# hdmi_to_8pin_header.net
KiCad netlist of a schematic drawn in Altium Designer
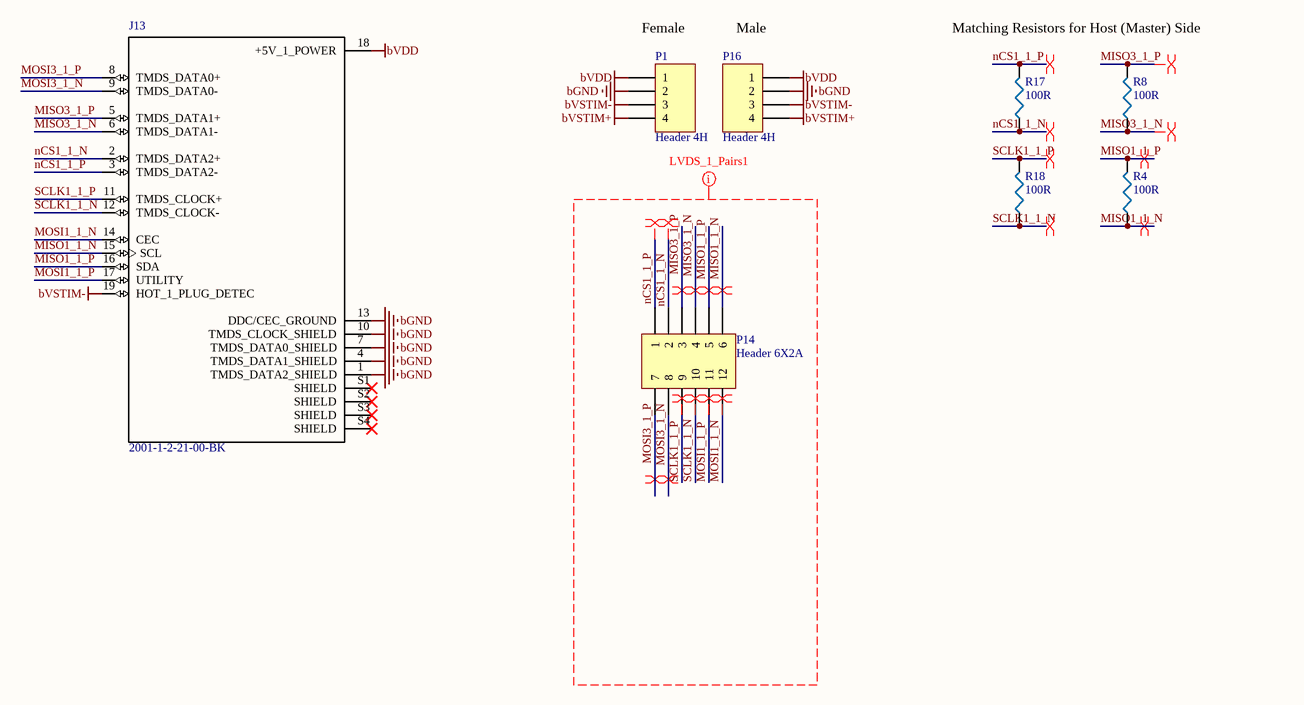
[diagram p0: hdmi_to_8pin_header.SchDoc]

(export (version "E")
  (design (tool "Eeschema 10.0.6"))
  (components
    (comp (ref "J13")
      (value "2001-1-2-21-00-BK")
      (footprint "*CNC_2001-1-2-21-00-BK_2001-1-2-21-00-BK(Primary)")
      (description "Mini Hdmi 19p Female Smt")
      (fields (field (name "DIGI-KEY_PART_NUMBER") "1175-1704-1-ND") (field (name "MANUFACTURER") "CNC Tech"))
      (libsource (lib "cnc_hdmi") (part "2001-1-2-21-00-BK"))
    )
    (comp (ref "P1")
      (value "Header 4H")
      (footprint "sullins_conn_headers:PPTC041LGBN-RC")
      (description "Header, 4-Pin, Right Angle")
      (fields
        (field (name "MANUFACTURER") "Sullins Connector Solutions")
        (field (name "MANUFACTURER PART NUMBER") "PPTC041LGBN-RC")
        (field (name "PUBLISHER") "Altium Limited")
      )
      (libsource (lib "") (part "Header 4H_1"))
    )
    (comp (ref "P14")
      (value "Header 6X2A")
      (footprint "sullins_conn_headers:PPPC062LJBN-RC")
      (description "Header, 6-Pin, Dual row")
      (fields
        (field (name "MANUFACTURER") "Sullins Connector Solutions")
        (field (name "MANUFACTURER PART NUMBER") "PPPC062LJBN-RC")
        (field (name "PUBLISHER") "Altium Limited")
      )
      (libsource (lib "Miscellaneous Connectors") (part "Header 6X2A"))
    )
    (comp (ref "P16")
      (value "Header 4H")
      (footprint "sullins_conn_headers:PEC04SBAN")
      (description "Header, 4-Pin, Right Angle")
      (fields
        (field (name "MANUFACTURER") "Sullins Connector Solutions")
        (field (name "MANUFACTURER PART NUMBER") "PEC04SBAN")
        (field (name "PUBLISHER") "Altium Limited")
      )
      (libsource (lib "Miscellaneous Connectors") (part "Header 4H"))
    )
    (comp (ref "R4")
      (value "100R")
      (footprint "standard_components:R0805")
      (description "ERJ-6ENF1000V")
      (fields (field (name "MANUFACTURER") "Panasonic Electronic Components") (field (name "TOLERANCE") "1%"))
      (libsource (lib "standard_components") (part "RES100"))
    )
    (comp (ref "R8")
      (value "100R")
      (footprint "standard_components:R0805")
      (description "ERJ-6ENF1000V")
      (fields (field (name "MANUFACTURER") "Panasonic Electronic Components") (field (name "TOLERANCE") "1%"))
      (libsource (lib "standard_components") (part "RES100"))
    )
    (comp (ref "R17")
      (value "100R")
      (footprint "standard_components:R0805")
      (description "ERJ-6ENF1000V")
      (fields (field (name "MANUFACTURER") "Panasonic Electronic Components") (field (name "TOLERANCE") "1%"))
      (libsource (lib "standard_components") (part "RES100"))
    )
    (comp (ref "R18")
      (value "100R")
      (footprint "standard_components:R0805")
      (description "ERJ-6ENF1000V")
      (fields (field (name "MANUFACTURER") "Panasonic Electronic Components") (field (name "TOLERANCE") "1%"))
      (libsource (lib "standard_components") (part "RES100"))
    )
  )
  (nets
    (net (code "1") (name "/MISO1_1_N") (class "Default")
      (node (ref "J13") (pin "15") (pinfunction "SCL_15") (pintype "bidirectional"))
      (node (ref "P14") (pin "6") (pinfunction "6_6") (pintype "passive"))
      (node (ref "R4") (pin "1") (pinfunction "1_1") (pintype "passive"))
    )
    (net (code "2") (name "/MISO1_1_P") (class "Default")
      (node (ref "J13") (pin "16") (pinfunction "SDA_16") (pintype "bidirectional"))
      (node (ref "P14") (pin "5") (pinfunction "5_5") (pintype "passive"))
      (node (ref "R4") (pin "2") (pinfunction "2_2") (pintype "passive"))
    )
    (net (code "3") (name "/MISO3_1_N") (class "Default")
      (node (ref "J13") (pin "6") (pinfunction "TMDS_DATA1-_6") (pintype "bidirectional"))
      (node (ref "P14") (pin "4") (pinfunction "4_4") (pintype "passive"))
      (node (ref "R8") (pin "1") (pinfunction "1_1") (pintype "passive"))
    )
    (net (code "4") (name "/MISO3_1_P") (class "Default")
      (node (ref "J13") (pin "5") (pinfunction "TMDS_DATA1+_5") (pintype "bidirectional"))
      (node (ref "P14") (pin "3") (pinfunction "3_3") (pintype "passive"))
      (node (ref "R8") (pin "2") (pinfunction "2_2") (pintype "passive"))
    )
    (net (code "5") (name "/MOSI1_1_N") (class "Default")
      (node (ref "J13") (pin "14") (pinfunction "CEC_14") (pintype "bidirectional"))
      (node (ref "P14") (pin "12") (pinfunction "12_12") (pintype "passive"))
    )
    (net (code "6") (name "/MOSI1_1_P") (class "Default")
      (node (ref "J13") (pin "17") (pinfunction "UTILITY_17") (pintype "bidirectional"))
      (node (ref "P14") (pin "11") (pinfunction "11_11") (pintype "passive"))
    )
    (net (code "7") (name "/MOSI3_1_N") (class "Default")
      (node (ref "J13") (pin "9") (pinfunction "TMDS_DATA0-_9") (pintype "bidirectional"))
      (node (ref "P14") (pin "8") (pinfunction "8_8") (pintype "passive"))
    )
    (net (code "8") (name "/MOSI3_1_P") (class "Default")
      (node (ref "J13") (pin "8") (pinfunction "TMDS_DATA0+_8") (pintype "bidirectional"))
      (node (ref "P14") (pin "7") (pinfunction "7_7") (pintype "passive"))
    )
    (net (code "9") (name "/SCLK1_1_N") (class "Default")
      (node (ref "J13") (pin "12") (pinfunction "TMDS_CLOCK-_12") (pintype "bidirectional"))
      (node (ref "P14") (pin "10") (pinfunction "10_10") (pintype "passive"))
      (node (ref "R18") (pin "1") (pinfunction "1_1") (pintype "passive"))
    )
    (net (code "10") (name "/SCLK1_1_P") (class "Default")
      (node (ref "J13") (pin "11") (pinfunction "TMDS_CLOCK+_11") (pintype "bidirectional"))
      (node (ref "P14") (pin "9") (pinfunction "9_9") (pintype "passive"))
      (node (ref "R18") (pin "2") (pinfunction "2_2") (pintype "passive"))
    )
    (net (code "11") (name "/nCS1_1_N") (class "Default")
      (node (ref "J13") (pin "2") (pinfunction "TMDS_DATA2+_2") (pintype "bidirectional"))
      (node (ref "P14") (pin "2") (pinfunction "2_2") (pintype "passive"))
      (node (ref "R17") (pin "1") (pinfunction "1_1") (pintype "passive"))
    )
    (net (code "12") (name "/nCS1_1_P") (class "Default")
      (node (ref "J13") (pin "3") (pinfunction "TMDS_DATA2-_3") (pintype "bidirectional"))
      (node (ref "P14") (pin "1") (pinfunction "1_1") (pintype "passive"))
      (node (ref "R17") (pin "2") (pinfunction "2_2") (pintype "passive"))
    )
    (net (code "13") (name "bGND") (class "Default")
      (node (ref "J13") (pin "1") (pinfunction "TMDS_DATA2_SHIELD_1") (pintype "power_in"))
      (node (ref "J13") (pin "10") (pinfunction "TMDS_CLOCK_SHIELD_10") (pintype "power_in"))
      (node (ref "J13") (pin "13") (pinfunction "DDC/CEC_GROUND_13") (pintype "power_in"))
      (node (ref "J13") (pin "4") (pinfunction "TMDS_DATA1_SHIELD_4") (pintype "power_in"))
      (node (ref "J13") (pin "7") (pinfunction "TMDS_DATA0_SHIELD_7") (pintype "power_in"))
      (node (ref "P1") (pin "2") (pinfunction "2_2") (pintype "passive"))
      (node (ref "P16") (pin "2") (pinfunction "2_2") (pintype "passive"))
    )
    (net (code "14") (name "bVDD") (class "Default")
      (node (ref "J13") (pin "18") (pinfunction "+5V_1_POWER_18") (pintype "power_in"))
      (node (ref "P1") (pin "1") (pinfunction "1_1") (pintype "passive"))
      (node (ref "P16") (pin "1") (pinfunction "1_1") (pintype "passive"))
    )
    (net (code "15") (name "bVSTIM+") (class "Default")
      (node (ref "P1") (pin "4") (pinfunction "4_4") (pintype "passive"))
      (node (ref "P16") (pin "4") (pinfunction "4_4") (pintype "passive"))
    )
    (net (code "16") (name "bVSTIM-") (class "Default")
      (node (ref "J13") (pin "19") (pinfunction "HOT_1_PLUG_DETEC_19") (pintype "bidirectional"))
      (node (ref "P1") (pin "3") (pinfunction "3_3") (pintype "passive"))
      (node (ref "P16") (pin "3") (pinfunction "3_3") (pintype "passive"))
    )
    (net (code "17") (name "unconnected-(J13-SHIELD-PadS1)") (class "Default")
      (node (ref "J13") (pin "S1") (pinfunction "SHIELD_S1") (pintype "power_in+no_connect"))
    )
    (net (code "18") (name "unconnected-(J13-SHIELD-PadS2)") (class "Default")
      (node (ref "J13") (pin "S2") (pinfunction "SHIELD_S2") (pintype "power_in+no_connect"))
    )
    (net (code "19") (name "unconnected-(J13-SHIELD-PadS3)") (class "Default")
      (node (ref "J13") (pin "S3") (pinfunction "SHIELD_S3") (pintype "power_in+no_connect"))
    )
    (net (code "20") (name "unconnected-(J13-SHIELD-PadS4)") (class "Default")
      (node (ref "J13") (pin "S4") (pinfunction "SHIELD_S4") (pintype "power_in+no_connect"))
    )
  )
)
